# ASM2022.net
KiCad netlist of a schematic drawn in EAGLE
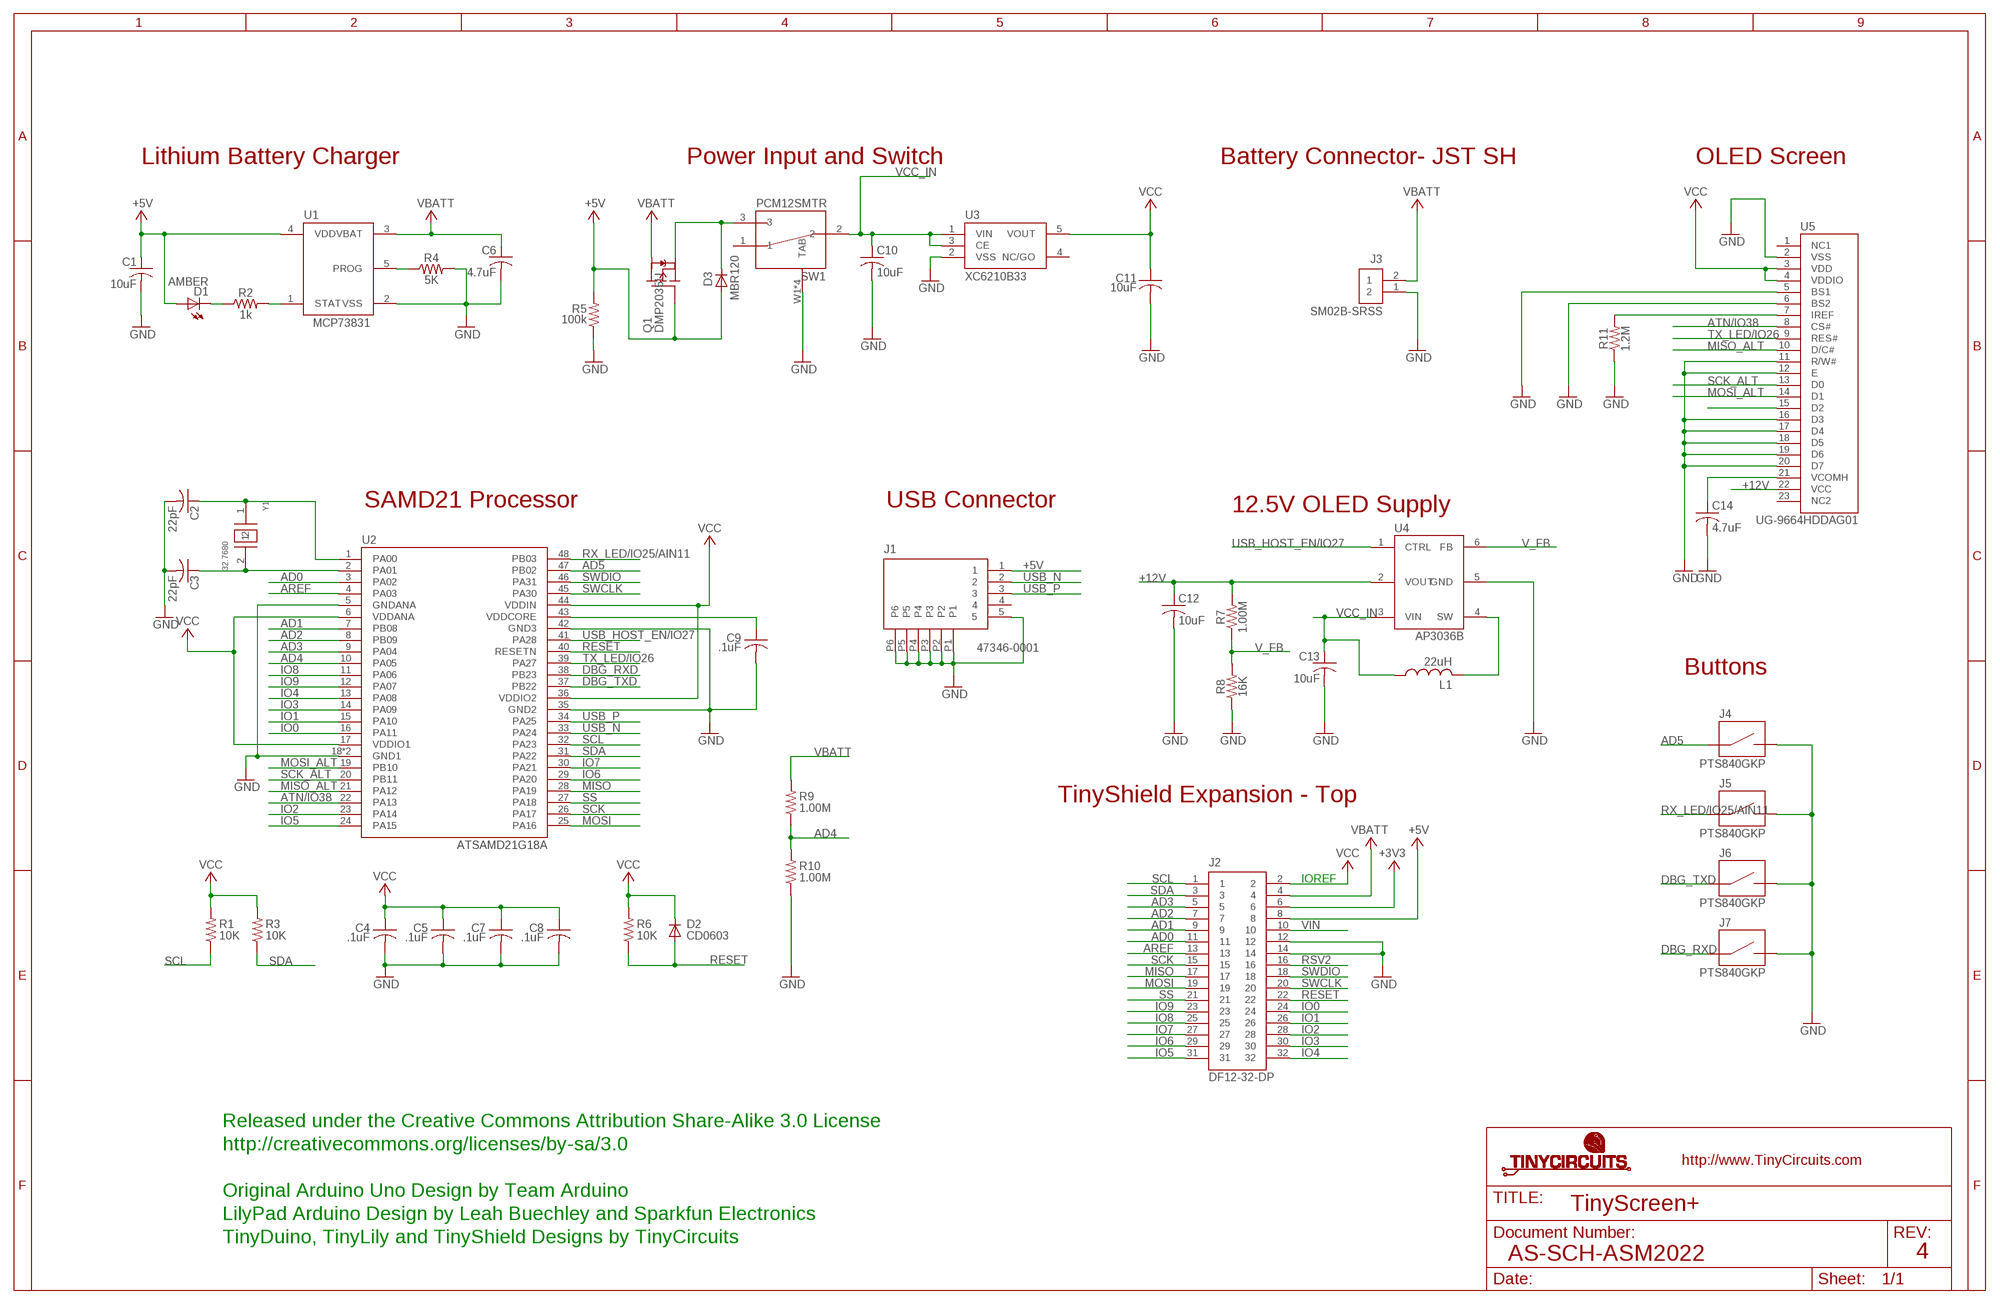
[diagram p0: schematic, sheet 1]

(export (version "E")
  (design (tool "Eeschema 10.0.6"))
  (components
    (comp (ref "C1")
      (value "10uF")
      (footprint "eagle-import:C0603")
      (fields (field (name "PARTNO") "AS-ITM-00002") (field (name "PARTNO_1") "AS-ITM-00002"))
      (libsource (lib "eagle-import") (part "AS-ITM-00002"))
    )
    (comp (ref "C2")
      (value "22pF")
      (footprint "eagle-import:C0402")
      (fields (field (name "PARTNO") "AS-ITM-00211") (field (name "PARTNO_1") "AS-ITM-00211"))
      (libsource (lib "eagle-import") (part "AS-ITM-00211"))
    )
    (comp (ref "C3")
      (value "22pF")
      (footprint "eagle-import:C0402")
      (fields (field (name "PARTNO") "AS-ITM-00211") (field (name "PARTNO_1") "AS-ITM-00211"))
      (libsource (lib "eagle-import") (part "AS-ITM-00211"))
    )
    (comp (ref "C4")
      (value ".1uF")
      (footprint "eagle-import:C0402")
      (fields (field (name "PARTNO") "AS-ITM-00008") (field (name "PARTNO_1") "AS-ITM-00008"))
      (libsource (lib "eagle-import") (part "AS-ITM-00008"))
    )
    (comp (ref "C5")
      (value ".1uF")
      (footprint "eagle-import:C0402")
      (fields (field (name "PARTNO") "AS-ITM-00008") (field (name "PARTNO_1") "AS-ITM-00008"))
      (libsource (lib "eagle-import") (part "AS-ITM-00008"))
    )
    (comp (ref "C6")
      (value "4.7uF")
      (footprint "eagle-import:C0603")
      (fields (field (name "PARTNO") "AS-ITM-00088") (field (name "PARTNO_1") "AS-ITM-00088"))
      (libsource (lib "eagle-import") (part "AS-ITM-00088"))
    )
    (comp (ref "C7")
      (value ".1uF")
      (footprint "eagle-import:C0402")
      (fields (field (name "PARTNO") "AS-ITM-00008") (field (name "PARTNO_1") "AS-ITM-00008"))
      (libsource (lib "eagle-import") (part "AS-ITM-00008"))
    )
    (comp (ref "C8")
      (value ".1uF")
      (footprint "eagle-import:C0402")
      (fields (field (name "PARTNO") "AS-ITM-00008") (field (name "PARTNO_1") "AS-ITM-00008"))
      (libsource (lib "eagle-import") (part "AS-ITM-00008"))
    )
    (comp (ref "C9")
      (value ".1uF")
      (footprint "eagle-import:C0402")
      (fields (field (name "PARTNO") "AS-ITM-00008") (field (name "PARTNO_1") "AS-ITM-00008"))
      (libsource (lib "eagle-import") (part "AS-ITM-00008"))
    )
    (comp (ref "C10")
      (value "10uF")
      (footprint "eagle-import:C0805")
      (fields (field (name "PARTNO") "AS-ITM-00045") (field (name "PARTNO_1") "AS-ITM-00045"))
      (libsource (lib "eagle-import") (part "AS-ITM-00045"))
    )
    (comp (ref "C11")
      (value "10uF")
      (footprint "eagle-import:C0603")
      (fields (field (name "PARTNO") "AS-ITM-00002") (field (name "PARTNO_1") "AS-ITM-00002"))
      (libsource (lib "eagle-import") (part "AS-ITM-00002"))
    )
    (comp (ref "C12")
      (value "10uF")
      (footprint "eagle-import:C0805")
      (fields (field (name "PARTNO") "AS-ITM-00045") (field (name "PARTNO_1") "AS-ITM-00045"))
      (libsource (lib "eagle-import") (part "AS-ITM-00045"))
    )
    (comp (ref "C13")
      (value "10uF")
      (footprint "eagle-import:C0603")
      (fields (field (name "PARTNO") "AS-ITM-00002") (field (name "PARTNO_1") "AS-ITM-00002"))
      (libsource (lib "eagle-import") (part "AS-ITM-00002"))
    )
    (comp (ref "C14")
      (value "4.7uF")
      (footprint "eagle-import:1206_CAP_TANT")
      (fields (field (name "PARTNO") "AS-ITM-00232") (field (name "PARTNO_1") "AS-ITM-00232"))
      (libsource (lib "eagle-import") (part "AS-ITM-00232"))
    )
    (comp (ref "D1")
      (value "AMBER")
      (footprint "eagle-import:LNJ_LED")
      (fields (field (name "PARTNO") "AS-ITM-00026") (field (name "PARTNO_1") "AS-ITM-00026"))
      (libsource (lib "eagle-import") (part "AS-ITM-00026"))
    )
    (comp (ref "D2")
      (value "CD0603")
      (footprint "eagle-import:0603")
      (fields (field (name "PARTNO") "AS-ITM-00009") (field (name "PARTNO_1") "AS-ITM-00009"))
      (libsource (lib "eagle-import") (part "AS-ITM-00009"))
    )
    (comp (ref "D3")
      (value "MBR120")
      (footprint "eagle-import:SOD-123FL")
      (fields (field (name "PARTNO") "AS-ITM-00111"))
      (libsource (lib "eagle-import") (part "AS-ITM-00111"))
    )
    (comp (ref "J1")
      (value "47346-0001")
      (footprint "eagle-import:MICRO_USB")
      (fields (field (name "PARTNO") "AS-ITM-00021"))
      (libsource (lib "eagle-import") (part "AS-ITM-00021"))
    )
    (comp (ref "J2")
      (value "DF12-32-DP")
      (footprint "eagle-import:DF12-32-DP")
      (fields (field (name "PARTNO") "AS-ITM-00015") (field (name "PARTNO_1") "AS-ITM-00015"))
      (libsource (lib "eagle-import") (part "AS-ITM-00015"))
    )
    (comp (ref "J3")
      (value "SM02B-SRSS")
      (footprint "eagle-import:JST_SH_2X1")
      (fields (field (name "PARTNO") "AS-ITM-00231"))
      (libsource (lib "eagle-import") (part "AS-ITM-00231"))
    )
    (comp (ref "J4")
      (value "PTS840 GKP")
      (footprint "eagle-import:PTS840GKP")
      (fields (field (name "PARTNO") "AS-ITM-00236") (field (name "PARTNO_1") "AS-ITM-00236"))
      (libsource (lib "eagle-import") (part "AS-ITM-00236"))
    )
    (comp (ref "J5")
      (value "PTS840 GKP")
      (footprint "eagle-import:PTS840GKP")
      (fields (field (name "PARTNO") "AS-ITM-00236") (field (name "PARTNO_1") "AS-ITM-00236"))
      (libsource (lib "eagle-import") (part "AS-ITM-00236"))
    )
    (comp (ref "J6")
      (value "PTS840 GKP")
      (footprint "eagle-import:PTS840GKP")
      (fields (field (name "PARTNO") "AS-ITM-00236") (field (name "PARTNO_1") "AS-ITM-00236"))
      (libsource (lib "eagle-import") (part "AS-ITM-00236"))
    )
    (comp (ref "J7")
      (value "PTS840 GKP")
      (footprint "eagle-import:PTS840GKP")
      (fields (field (name "PARTNO") "AS-ITM-00236") (field (name "PARTNO_1") "AS-ITM-00236"))
      (libsource (lib "eagle-import") (part "AS-ITM-00236"))
    )
    (comp (ref "L1")
      (value "22uH")
      (footprint "eagle-import:R0805")
      (fields (field (name "PARTNO") "AS-ITM-00281"))
      (libsource (lib "eagle-import") (part "AS-ITM-00281"))
    )
    (comp (ref "Q1")
      (value "DMP2035U")
      (footprint "eagle-import:SOT23")
      (fields (field (name "PARTNO") "AS-ITM-00024"))
      (libsource (lib "eagle-import") (part "AS-ITM-00024"))
    )
    (comp (ref "R1")
      (value "10K")
      (footprint "eagle-import:0402")
      (fields (field (name "PARTNO") "AS-ITM-00032") (field (name "PARTNO_1") "AS-ITM-00032"))
      (libsource (lib "eagle-import") (part "AS-ITM-00032"))
    )
    (comp (ref "R2")
      (value "1k")
      (footprint "eagle-import:0402")
      (fields (field (name "PARTNO") "AS-ITM-00003") (field (name "PARTNO_1") "AS-ITM-00003"))
      (libsource (lib "eagle-import") (part "AS-ITM-00003"))
    )
    (comp (ref "R3")
      (value "10K")
      (footprint "eagle-import:0402")
      (fields (field (name "PARTNO") "AS-ITM-00032") (field (name "PARTNO_1") "AS-ITM-00032"))
      (libsource (lib "eagle-import") (part "AS-ITM-00032"))
    )
    (comp (ref "R4")
      (value "5K")
      (footprint "eagle-import:0402")
      (fields (field (name "PARTNO") "AS-ITM-00289"))
      (libsource (lib "eagle-import") (part "AS-ITM-00289"))
    )
    (comp (ref "R5")
      (value "100k")
      (footprint "eagle-import:0402")
      (fields (field (name "PARTNO") "AS-ITM-00004") (field (name "PARTNO_1") "AS-ITM-00004"))
      (libsource (lib "eagle-import") (part "AS-ITM-00004"))
    )
    (comp (ref "R6")
      (value "10K")
      (footprint "eagle-import:0402")
      (fields (field (name "PARTNO") "AS-ITM-00032") (field (name "PARTNO_1") "AS-ITM-00032"))
      (libsource (lib "eagle-import") (part "AS-ITM-00032"))
    )
    (comp (ref "R7")
      (value "1.00M")
      (footprint "eagle-import:0402")
      (fields (field (name "PARTNO") "AS-ITM-00005") (field (name "PARTNO_1") "AS-ITM-00005"))
      (libsource (lib "eagle-import") (part "AS-ITM-00005"))
    )
    (comp (ref "R8")
      (value "16K")
      (footprint "eagle-import:0402")
      (fields (field (name "PARTNO") "AS-ITM-00314") (field (name "PARTNO_1") "AS-ITM-00314"))
      (libsource (lib "eagle-import") (part "AS-ITM-00314"))
    )
    (comp (ref "R9")
      (value "1.00M")
      (footprint "eagle-import:0402")
      (fields (field (name "PARTNO") "AS-ITM-00005") (field (name "PARTNO_1") "AS-ITM-00005"))
      (libsource (lib "eagle-import") (part "AS-ITM-00005"))
    )
    (comp (ref "R10")
      (value "1.00M")
      (footprint "eagle-import:0402")
      (fields (field (name "PARTNO") "AS-ITM-00005") (field (name "PARTNO_1") "AS-ITM-00005"))
      (libsource (lib "eagle-import") (part "AS-ITM-00005"))
    )
    (comp (ref "R11")
      (value "1.2M")
      (footprint "eagle-import:0402")
      (fields (field (name "PARTNO") "AS-ITM-00280") (field (name "PARTNO_1") "AS-ITM-00280"))
      (libsource (lib "eagle-import") (part "AS-ITM-00280"))
    )
    (comp (ref "SW1")
      (value "PCM12SMTR")
      (footprint "eagle-import:PCM12SMTR")
      (fields (field (name "PARTNO") "AS-ITM-00220"))
      (libsource (lib "eagle-import") (part "AS-ITM-00220"))
    )
    (comp (ref "U1")
      (value "MCP73831")
      (footprint "eagle-import:SOT-23")
      (fields (field (name "PARTNO") "AS-ITM-00136"))
      (libsource (lib "eagle-import") (part "AS-ITM-00136"))
    )
    (comp (ref "U2")
      (value "ATSAMD21G18A")
      (footprint "eagle-import:QFN48")
      (fields (field (name "PARTNO") "AS-ITM-00273") (field (name "PARTNO_1") "AS-ITM-00273"))
      (libsource (lib "eagle-import") (part "AS-ITM-00273"))
    )
    (comp (ref "U3")
      (value "XC6210B33")
      (footprint "eagle-import:SOT-25")
      (fields (field (name "PARTNO") "AS-ITM-00046"))
      (libsource (lib "eagle-import") (part "AS-ITM-00046"))
    )
    (comp (ref "U4")
      (value "AP3036B")
      (footprint "eagle-import:SOT-23-6")
      (fields (field (name "PARTNO") "AS-ITM-00377") (field (name "PARTNO_1") "AS-ITM-00377"))
      (libsource (lib "eagle-import") (part "AS-ITM-00377"))
    )
    (comp (ref "U5")
      (value "UG-9664HDDAG01")
      (footprint "eagle-import:OLED_DISPLAY")
      (fields (field (name "PARTNO") "AS-ITM-00158"))
      (libsource (lib "eagle-import") (part "AS-ITM-00158"))
    )
    (comp (ref "Y1")
      (value "32.7680")
      (footprint "eagle-import:ABS06")
      (fields (field (name "PARTNO") "AS-ITM-00279") (field (name "PARTNO_1") "AS-ITM-00279"))
      (libsource (lib "eagle-import") (part "AS-ITM-00279"))
    )
  )
  (nets
    (net (code "1") (name "+3V3") (class "Default")
      (node (ref "J2") (pin "6") (pinfunction "6_6") (pintype "bidirectional"))
    )
    (net (code "2") (name "+5V") (class "Default")
      (node (ref "C1") (pin "1") (pinfunction "1_1") (pintype "passive"))
      (node (ref "D1") (pin "A") (pinfunction "A_A") (pintype "passive"))
      (node (ref "D3") (pin "A") (pinfunction "A_A") (pintype "passive"))
      (node (ref "J1") (pin "1") (pinfunction "1_1") (pintype "bidirectional"))
      (node (ref "J2") (pin "8") (pinfunction "8_8") (pintype "bidirectional"))
      (node (ref "Q1") (pin "B") (pinfunction "G_B") (pintype "passive"))
      (node (ref "R5") (pin "2") (pinfunction "2_2") (pintype "passive"))
      (node (ref "U1") (pin "4") (pinfunction "VDD_4") (pintype "bidirectional"))
    )
    (net (code "3") (name "/+12V") (class "Default")
      (node (ref "C12") (pin "1") (pinfunction "1_1") (pintype "passive"))
      (node (ref "R7") (pin "2") (pinfunction "2_2") (pintype "passive"))
      (node (ref "U4") (pin "2") (pinfunction "VOUT_2") (pintype "bidirectional"))
      (node (ref "U5") (pin "22") (pinfunction "VCC_22") (pintype "bidirectional"))
    )
    (net (code "4") (name "/AD0") (class "Default")
      (node (ref "J2") (pin "11") (pinfunction "11_11") (pintype "bidirectional"))
      (node (ref "U2") (pin "3") (pinfunction "PA02_3") (pintype "bidirectional"))
    )
    (net (code "5") (name "/AD1") (class "Default")
      (node (ref "J2") (pin "9") (pinfunction "9_9") (pintype "bidirectional"))
      (node (ref "U2") (pin "7") (pinfunction "PB08_7") (pintype "bidirectional"))
    )
    (net (code "6") (name "/AD2") (class "Default")
      (node (ref "J2") (pin "7") (pinfunction "7_7") (pintype "bidirectional"))
      (node (ref "U2") (pin "8") (pinfunction "PB09_8") (pintype "bidirectional"))
    )
    (net (code "7") (name "/AD3") (class "Default")
      (node (ref "J2") (pin "5") (pinfunction "5_5") (pintype "bidirectional"))
      (node (ref "U2") (pin "9") (pinfunction "PA04_9") (pintype "bidirectional"))
    )
    (net (code "8") (name "/AD4") (class "Default")
      (node (ref "R10") (pin "2") (pinfunction "2_2") (pintype "passive"))
      (node (ref "R9") (pin "1") (pinfunction "1_1") (pintype "passive"))
      (node (ref "U2") (pin "10") (pinfunction "PA05_10") (pintype "bidirectional"))
    )
    (net (code "9") (name "/AD5") (class "Default")
      (node (ref "J4") (pin "1") (pinfunction "1_1") (pintype "bidirectional"))
      (node (ref "J4") (pin "2") (pinfunction "1_2") (pintype "bidirectional"))
      (node (ref "U2") (pin "47") (pinfunction "PB02_47") (pintype "bidirectional"))
    )
    (net (code "10") (name "/AREF") (class "Default")
      (node (ref "J2") (pin "13") (pinfunction "13_13") (pintype "bidirectional"))
      (node (ref "U2") (pin "4") (pinfunction "PA03_4") (pintype "bidirectional"))
    )
    (net (code "11") (name "/ATN{slash}IO38") (class "Default")
      (node (ref "U2") (pin "22") (pinfunction "PA13_22") (pintype "bidirectional"))
      (node (ref "U5") (pin "8") (pinfunction "CS#_8") (pintype "bidirectional"))
    )
    (net (code "12") (name "/DBG_RXD") (class "Default")
      (node (ref "J7") (pin "1") (pinfunction "1_1") (pintype "bidirectional"))
      (node (ref "J7") (pin "2") (pinfunction "1_2") (pintype "bidirectional"))
      (node (ref "U2") (pin "38") (pinfunction "PB23_38") (pintype "bidirectional"))
    )
    (net (code "13") (name "/DBG_TXD") (class "Default")
      (node (ref "J6") (pin "1") (pinfunction "1_1") (pintype "bidirectional"))
      (node (ref "J6") (pin "2") (pinfunction "1_2") (pintype "bidirectional"))
      (node (ref "U2") (pin "37") (pinfunction "PB22_37") (pintype "bidirectional"))
    )
    (net (code "14") (name "/IO0") (class "Default")
      (node (ref "J2") (pin "24") (pinfunction "24_24") (pintype "bidirectional"))
      (node (ref "U2") (pin "16") (pinfunction "PA11_16") (pintype "bidirectional"))
    )
    (net (code "15") (name "/IO1") (class "Default")
      (node (ref "J2") (pin "26") (pinfunction "26_26") (pintype "bidirectional"))
      (node (ref "U2") (pin "15") (pinfunction "PA10_15") (pintype "bidirectional"))
    )
    (net (code "16") (name "/IO2") (class "Default")
      (node (ref "J2") (pin "28") (pinfunction "28_28") (pintype "bidirectional"))
      (node (ref "U2") (pin "23") (pinfunction "PA14_23") (pintype "bidirectional"))
    )
    (net (code "17") (name "/IO3") (class "Default")
      (node (ref "J2") (pin "30") (pinfunction "30_30") (pintype "bidirectional"))
      (node (ref "U2") (pin "14") (pinfunction "PA09_14") (pintype "bidirectional"))
    )
    (net (code "18") (name "/IO4") (class "Default")
      (node (ref "J2") (pin "32") (pinfunction "32_32") (pintype "bidirectional"))
      (node (ref "U2") (pin "13") (pinfunction "PA08_13") (pintype "bidirectional"))
    )
    (net (code "19") (name "/IO5") (class "Default")
      (node (ref "J2") (pin "31") (pinfunction "31_31") (pintype "bidirectional"))
      (node (ref "U2") (pin "24") (pinfunction "PA15_24") (pintype "bidirectional"))
    )
    (net (code "20") (name "/IO6") (class "Default")
      (node (ref "J2") (pin "29") (pinfunction "29_29") (pintype "bidirectional"))
      (node (ref "U2") (pin "29") (pinfunction "PA20_29") (pintype "bidirectional"))
    )
    (net (code "21") (name "/IO7") (class "Default")
      (node (ref "J2") (pin "27") (pinfunction "27_27") (pintype "bidirectional"))
      (node (ref "U2") (pin "30") (pinfunction "PA21_30") (pintype "bidirectional"))
    )
    (net (code "22") (name "/IO8") (class "Default")
      (node (ref "J2") (pin "25") (pinfunction "25_25") (pintype "bidirectional"))
      (node (ref "U2") (pin "11") (pinfunction "PA06_11") (pintype "bidirectional"))
    )
    (net (code "23") (name "/IO9") (class "Default")
      (node (ref "J2") (pin "23") (pinfunction "23_23") (pintype "bidirectional"))
      (node (ref "U2") (pin "12") (pinfunction "PA07_12") (pintype "bidirectional"))
    )
    (net (code "24") (name "/MISO") (class "Default")
      (node (ref "J2") (pin "17") (pinfunction "17_17") (pintype "bidirectional"))
      (node (ref "U2") (pin "28") (pinfunction "PA19_28") (pintype "bidirectional"))
    )
    (net (code "25") (name "/MISO_ALT") (class "Default")
      (node (ref "U2") (pin "21") (pinfunction "PA12_21") (pintype "bidirectional"))
      (node (ref "U5") (pin "10") (pinfunction "D/C#_10") (pintype "bidirectional"))
    )
    (net (code "26") (name "/MOSI") (class "Default")
      (node (ref "J2") (pin "19") (pinfunction "19_19") (pintype "bidirectional"))
      (node (ref "U2") (pin "25") (pinfunction "PA16_25") (pintype "bidirectional"))
    )
    (net (code "27") (name "/MOSI_ALT") (class "Default")
      (node (ref "U2") (pin "19") (pinfunction "PB10_19") (pintype "bidirectional"))
      (node (ref "U5") (pin "14") (pinfunction "D1_14") (pintype "bidirectional"))
    )
    (net (code "28") (name "/RESET") (class "Default")
      (node (ref "D2") (pin "A") (pinfunction "A_A") (pintype "passive"))
      (node (ref "J2") (pin "22") (pinfunction "22_22") (pintype "bidirectional"))
      (node (ref "R6") (pin "1") (pinfunction "1_1") (pintype "passive"))
      (node (ref "U2") (pin "40") (pinfunction "RESETN_40") (pintype "bidirectional"))
    )
    (net (code "29") (name "/RSV2") (class "Default")
      (node (ref "J2") (pin "16") (pinfunction "16_16") (pintype "bidirectional"))
    )
    (net (code "30") (name "/RX_LED{slash}IO25{slash}AIN11") (class "Default")
      (node (ref "J5") (pin "1") (pinfunction "1_1") (pintype "bidirectional"))
      (node (ref "J5") (pin "2") (pinfunction "1_2") (pintype "bidirectional"))
      (node (ref "U2") (pin "48") (pinfunction "PB03_48") (pintype "bidirectional"))
    )
    (net (code "31") (name "/SCK") (class "Default")
      (node (ref "J2") (pin "15") (pinfunction "15_15") (pintype "bidirectional"))
      (node (ref "U2") (pin "26") (pinfunction "PA17_26") (pintype "bidirectional"))
    )
    (net (code "32") (name "/SCK_ALT") (class "Default")
      (node (ref "U2") (pin "20") (pinfunction "PB11_20") (pintype "bidirectional"))
      (node (ref "U5") (pin "13") (pinfunction "D0_13") (pintype "bidirectional"))
    )
    (net (code "33") (name "/SCL") (class "Default")
      (node (ref "J2") (pin "1") (pinfunction "1_1") (pintype "bidirectional"))
      (node (ref "R1") (pin "1") (pinfunction "1_1") (pintype "passive"))
      (node (ref "U2") (pin "32") (pinfunction "PA23_32") (pintype "bidirectional"))
    )
    (net (code "34") (name "/SDA") (class "Default")
      (node (ref "J2") (pin "3") (pinfunction "3_3") (pintype "bidirectional"))
      (node (ref "R3") (pin "1") (pinfunction "1_1") (pintype "passive"))
      (node (ref "U2") (pin "31") (pinfunction "PA22_31") (pintype "bidirectional"))
    )
    (net (code "35") (name "/SS") (class "Default")
      (node (ref "J2") (pin "21") (pinfunction "21_21") (pintype "bidirectional"))
      (node (ref "U2") (pin "27") (pinfunction "PA18_27") (pintype "bidirectional"))
    )
    (net (code "36") (name "/SWCLK") (class "Default")
      (node (ref "J2") (pin "20") (pinfunction "20_20") (pintype "bidirectional"))
      (node (ref "U2") (pin "45") (pinfunction "PA30_45") (pintype "bidirectional"))
    )
    (net (code "37") (name "/SWDIO") (class "Default")
      (node (ref "J2") (pin "18") (pinfunction "18_18") (pintype "bidirectional"))
      (node (ref "U2") (pin "46") (pinfunction "PA31_46") (pintype "bidirectional"))
    )
    (net (code "38") (name "/TX_LED{slash}IO26") (class "Default")
      (node (ref "U2") (pin "39") (pinfunction "PA27_39") (pintype "bidirectional"))
      (node (ref "U5") (pin "9") (pinfunction "RES#_9") (pintype "bidirectional"))
    )
    (net (code "39") (name "/USB_HOST_EN{slash}IO27") (class "Default")
      (node (ref "U2") (pin "41") (pinfunction "PA28_41") (pintype "bidirectional"))
      (node (ref "U4") (pin "1") (pinfunction "CTRL_1") (pintype "bidirectional"))
    )
    (net (code "40") (name "/USB_N") (class "Default")
      (node (ref "J1") (pin "2") (pinfunction "2_2") (pintype "bidirectional"))
      (node (ref "U2") (pin "33") (pinfunction "PA24_33") (pintype "bidirectional"))
    )
    (net (code "41") (name "/USB_P") (class "Default")
      (node (ref "J1") (pin "3") (pinfunction "3_3") (pintype "bidirectional"))
      (node (ref "U2") (pin "34") (pinfunction "PA25_34") (pintype "bidirectional"))
    )
    (net (code "42") (name "/VCC_IN") (class "Default")
      (node (ref "C10") (pin "1") (pinfunction "1_1") (pintype "passive"))
      (node (ref "C13") (pin "1") (pinfunction "1_1") (pintype "passive"))
      (node (ref "L1") (pin "1") (pinfunction "1_1") (pintype "passive"))
      (node (ref "SW1") (pin "2") (pinfunction "2_2") (pintype "bidirectional"))
      (node (ref "U3") (pin "1") (pinfunction "VIN_1") (pintype "bidirectional"))
      (node (ref "U3") (pin "3") (pinfunction "CE_3") (pintype "bidirectional"))
      (node (ref "U4") (pin "3") (pinfunction "VIN_3") (pintype "bidirectional"))
    )
    (net (code "43") (name "/VIN") (class "Default")
      (node (ref "J2") (pin "10") (pinfunction "10_10") (pintype "bidirectional"))
    )
    (net (code "44") (name "/V_FB") (class "Default")
      (node (ref "R7") (pin "1") (pinfunction "1_1") (pintype "passive"))
      (node (ref "R8") (pin "2") (pinfunction "2_2") (pintype "passive"))
      (node (ref "U4") (pin "6") (pinfunction "FB_6") (pintype "bidirectional"))
    )
    (net (code "45") (name "GND") (class "Default")
      (node (ref "C1") (pin "2") (pinfunction "2_2") (pintype "passive"))
      (node (ref "C10") (pin "2") (pinfunction "2_2") (pintype "passive"))
      (node (ref "C11") (pin "2") (pinfunction "2_2") (pintype "passive"))
      (node (ref "C12") (pin "2") (pinfunction "2_2") (pintype "passive"))
      (node (ref "C13") (pin "2") (pinfunction "2_2") (pintype "passive"))
      (node (ref "C14") (pin "2") (pinfunction "2_2") (pintype "passive"))
      (node (ref "C2") (pin "2") (pinfunction "2_2") (pintype "passive"))
      (node (ref "C3") (pin "2") (pinfunction "2_2") (pintype "passive"))
      (node (ref "C4") (pin "2") (pinfunction "2_2") (pintype "passive"))
      (node (ref "C5") (pin "2") (pinfunction "2_2") (pintype "passive"))
      (node (ref "C6") (pin "2") (pinfunction "2_2") (pintype "passive"))
      (node (ref "C7") (pin "2") (pinfunction "2_2") (pintype "passive"))
      (node (ref "C8") (pin "2") (pinfunction "2_2") (pintype "passive"))
      (node (ref "C9") (pin "2") (pinfunction "2_2") (pintype "passive"))
      (node (ref "J1") (pin "5") (pinfunction "5_5") (pintype "bidirectional"))
      (node (ref "J1") (pin "P1") (pinfunction "P1_P1") (pintype "bidirectional"))
      (node (ref "J1") (pin "P2") (pinfunction "P2_P2") (pintype "bidirectional"))
      (node (ref "J1") (pin "P3") (pinfunction "P3_P3") (pintype "bidirectional"))
      (node (ref "J1") (pin "P4") (pinfunction "P4_P4") (pintype "bidirectional"))
      (node (ref "J1") (pin "P5") (pinfunction "P5_P5") (pintype "bidirectional"))
      (node (ref "J1") (pin "P6") (pinfunction "P6_P6") (pintype "bidirectional"))
      (node (ref "J2") (pin "12") (pinfunction "12_12") (pintype "bidirectional"))
      (node (ref "J2") (pin "14") (pinfunction "14_14") (pintype "bidirectional"))
      (node (ref "J3") (pin "1") (pinfunction "2_1") (pintype "bidirectional"))
      (node (ref "J4") (pin "3") (pinfunction "2_3") (pintype "bidirectional"))
      (node (ref "J4") (pin "4") (pinfunction "2_4") (pintype "bidirectional"))
      (node (ref "J5") (pin "3") (pinfunction "2_3") (pintype "bidirectional"))
      (node (ref "J5") (pin "4") (pinfunction "2_4") (pintype "bidirectional"))
      (node (ref "J6") (pin "3") (pinfunction "2_3") (pintype "bidirectional"))
      (node (ref "J6") (pin "4") (pinfunction "2_4") (pintype "bidirectional"))
      (node (ref "J7") (pin "3") (pinfunction "2_3") (pintype "bidirectional"))
      (node (ref "J7") (pin "4") (pinfunction "2_4") (pintype "bidirectional"))
      (node (ref "R10") (pin "1") (pinfunction "1_1") (pintype "passive"))
      (node (ref "R11") (pin "1") (pinfunction "1_1") (pintype "passive"))
      (node (ref "R4") (pin "2") (pinfunction "2_2") (pintype "passive"))
      (node (ref "R5") (pin "1") (pinfunction "1_1") (pintype "passive"))
      (node (ref "R8") (pin "1") (pinfunction "1_1") (pintype "passive"))
      (node (ref "SW1") (pin "W1") (pinfunction "TAB_W1") (pintype "bidirectional"))
      (node (ref "SW1") (pin "W2") (pinfunction "TAB_W2") (pintype "bidirectional"))
      (node (ref "SW1") (pin "W3") (pinfunction "TAB_W3") (pintype "bidirectional"))
      (node (ref "SW1") (pin "W4") (pinfunction "TAB_W4") (pintype "bidirectional"))
      (node (ref "U1") (pin "2") (pinfunction "VSS_2") (pintype "bidirectional"))
      (node (ref "U2") (pin "18") (pinfunction "GND1_18") (pintype "bidirectional"))
      (node (ref "U2") (pin "35") (pinfunction "GND2_35") (pintype "bidirectional"))
      (node (ref "U2") (pin "42") (pinfunction "GND3_42") (pintype "bidirectional"))
      (node (ref "U2") (pin "5") (pinfunction "GNDANA_5") (pintype "bidirectional"))
      (node (ref "U2") (pin "EXP") (pinfunction "GND1_EXP") (pintype "bidirectional"))
      (node (ref "U3") (pin "2") (pinfunction "VSS_2") (pintype "power_in"))
      (node (ref "U4") (pin "5") (pinfunction "GND_5") (pintype "bidirectional"))
      (node (ref "U5") (pin "11") (pinfunction "R/W#_11") (pintype "bidirectional"))
      (node (ref "U5") (pin "12") (pinfunction "E_12") (pintype "bidirectional"))
      (node (ref "U5") (pin "16") (pinfunction "D3_16") (pintype "bidirectional"))
      (node (ref "U5") (pin "17") (pinfunction "D4_17") (pintype "bidirectional"))
      (node (ref "U5") (pin "18") (pinfunction "D5_18") (pintype "bidirectional"))
      (node (ref "U5") (pin "19") (pinfunction "D6_19") (pintype "bidirectional"))
      (node (ref "U5") (pin "2") (pinfunction "VSS_2") (pintype "bidirectional"))
      (node (ref "U5") (pin "20") (pinfunction "D7_20") (pintype "bidirectional"))
      (node (ref "U5") (pin "5") (pinfunction "BS1_5") (pintype "bidirectional"))
      (node (ref "U5") (pin "6") (pinfunction "BS2_6") (pintype "bidirectional"))
    )
    (net (code "46") (name "Net-(D1-PadC)") (class "Default")
      (node (ref "D1") (pin "C") (pinfunction "C_C") (pintype "passive"))
      (node (ref "R2") (pin "1") (pinfunction "1_1") (pintype "passive"))
    )
    (net (code "47") (name "Net-(Q1-S)") (class "Default")
      (node (ref "D3") (pin "C") (pinfunction "C_C") (pintype "passive"))
      (node (ref "Q1") (pin "E") (pinfunction "S_E") (pintype "passive"))
      (node (ref "SW1") (pin "3") (pinfunction "3_3") (pintype "bidirectional"))
    )
    (net (code "48") (name "Net-(U1-PROG)") (class "Default")
      (node (ref "R4") (pin "1") (pinfunction "1_1") (pintype "passive"))
      (node (ref "U1") (pin "5") (pinfunction "PROG_5") (pintype "bidirectional"))
    )
    (net (code "49") (name "Net-(U1-STAT)") (class "Default")
      (node (ref "R2") (pin "2") (pinfunction "2_2") (pintype "passive"))
      (node (ref "U1") (pin "1") (pinfunction "STAT_1") (pintype "bidirectional"))
    )
    (net (code "50") (name "Net-(U2-PA00)") (class "Default")
      (node (ref "C2") (pin "1") (pinfunction "1_1") (pintype "passive"))
      (node (ref "U2") (pin "1") (pinfunction "PA00_1") (pintype "bidirectional"))
      (node (ref "Y1") (pin "1") (pinfunction "1_1") (pintype "bidirectional"))
    )
    (net (code "51") (name "Net-(U2-PA01)") (class "Default")
      (node (ref "C3") (pin "1") (pinfunction "1_1") (pintype "passive"))
      (node (ref "U2") (pin "2") (pinfunction "PA01_2") (pintype "bidirectional"))
      (node (ref "Y1") (pin "2") (pinfunction "2_2") (pintype "bidirectional"))
    )
    (net (code "52") (name "Net-(U2-VDDCORE)") (class "Default")
      (node (ref "C9") (pin "1") (pinfunction "1_1") (pintype "passive"))
      (node (ref "U2") (pin "43") (pinfunction "VDDCORE_43") (pintype "bidirectional"))
    )
    (net (code "53") (name "Net-(U4-SW)") (class "Default")
      (node (ref "L1") (pin "2") (pinfunction "2_2") (pintype "passive"))
      (node (ref "U4") (pin "4") (pinfunction "SW_4") (pintype "bidirectional"))
    )
    (net (code "54") (name "Net-(U5-IREF)") (class "Default")
      (node (ref "R11") (pin "2") (pinfunction "2_2") (pintype "passive"))
      (node (ref "U5") (pin "7") (pinfunction "IREF_7") (pintype "bidirectional"))
    )
    (net (code "55") (name "Net-(U5-VCOMH)") (class "Default")
      (node (ref "C14") (pin "1") (pinfunction "1_1") (pintype "passive"))
      (node (ref "U5") (pin "21") (pinfunction "VCOMH_21") (pintype "bidirectional"))
    )
    (net (code "56") (name "VBATT") (class "Default")
      (node (ref "C6") (pin "1") (pinfunction "1_1") (pintype "passive"))
      (node (ref "J2") (pin "4") (pinfunction "4_4") (pintype "bidirectional"))
      (node (ref "J3") (pin "2") (pinfunction "1_2") (pintype "bidirectional"))
      (node (ref "Q1") (pin "C") (pinfunction "D_C") (pintype "passive"))
      (node (ref "R9") (pin "2") (pinfunction "2_2") (pintype "passive"))
      (node (ref "U1") (pin "3") (pinfunction "VBAT_3") (pintype "bidirectional"))
    )
    (net (code "57") (name "VCC") (class "Default")
      (node (ref "C11") (pin "1") (pinfunction "1_1") (pintype "passive"))
      (node (ref "C4") (pin "1") (pinfunction "1_1") (pintype "passive"))
      (node (ref "C5") (pin "1") (pinfunction "1_1") (pintype "passive"))
      (node (ref "C7") (pin "1") (pinfunction "1_1") (pintype "passive"))
      (node (ref "C8") (pin "1") (pinfunction "1_1") (pintype "passive"))
      (node (ref "D2") (pin "C") (pinfunction "C_C") (pintype "passive"))
      (node (ref "J2") (pin "2") (pinfunction "2_2") (pintype "bidirectional"))
      (node (ref "R1") (pin "2") (pinfunction "2_2") (pintype "passive"))
      (node (ref "R3") (pin "2") (pinfunction "2_2") (pintype "passive"))
      (node (ref "R6") (pin "2") (pinfunction "2_2") (pintype "passive"))
      (node (ref "U2") (pin "17") (pinfunction "VDDIO1_17") (pintype "bidirectional"))
      (node (ref "U2") (pin "36") (pinfunction "VDDIO2_36") (pintype "bidirectional"))
      (node (ref "U2") (pin "44") (pinfunction "VDDIN_44") (pintype "bidirectional"))
      (node (ref "U2") (pin "6") (pinfunction "VDDANA_6") (pintype "bidirectional"))
      (node (ref "U3") (pin "5") (pinfunction "VOUT_5") (pintype "bidirectional"))
      (node (ref "U5") (pin "3") (pinfunction "VDD_3") (pintype "bidirectional"))
      (node (ref "U5") (pin "4") (pinfunction "VDDIO_4") (pintype "bidirectional"))
    )
    (net (code "58") (name "unconnected-(J1-Pad4)") (class "Default")
      (node (ref "J1") (pin "4") (pinfunction "4_4") (pintype "bidirectional"))
    )
    (net (code "59") (name "unconnected-(SW1-Pad1)") (class "Default")
      (node (ref "SW1") (pin "1") (pinfunction "1_1") (pintype "bidirectional"))
    )
    (net (code "60") (name "unconnected-(U3-NC{slash}GO-Pad4)") (class "Default")
      (node (ref "U3") (pin "4") (pinfunction "NC/GO_4") (pintype "bidirectional"))
    )
    (net (code "61") (name "unconnected-(U5-D2-Pad15)") (class "Default")
      (node (ref "U5") (pin "15") (pinfunction "D2_15") (pintype "bidirectional"))
    )
    (net (code "62") (name "unconnected-(U5-NC1-Pad1)") (class "Default")
      (node (ref "U5") (pin "1") (pinfunction "NC1_1") (pintype "bidirectional"))
    )
    (net (code "63") (name "unconnected-(U5-NC2-Pad23)") (class "Default")
      (node (ref "U5") (pin "23") (pinfunction "NC2_23") (pintype "bidirectional"))
    )
  )
)
